# blimpy.net
KiCad netlist of a schematic drawn in EAGLE
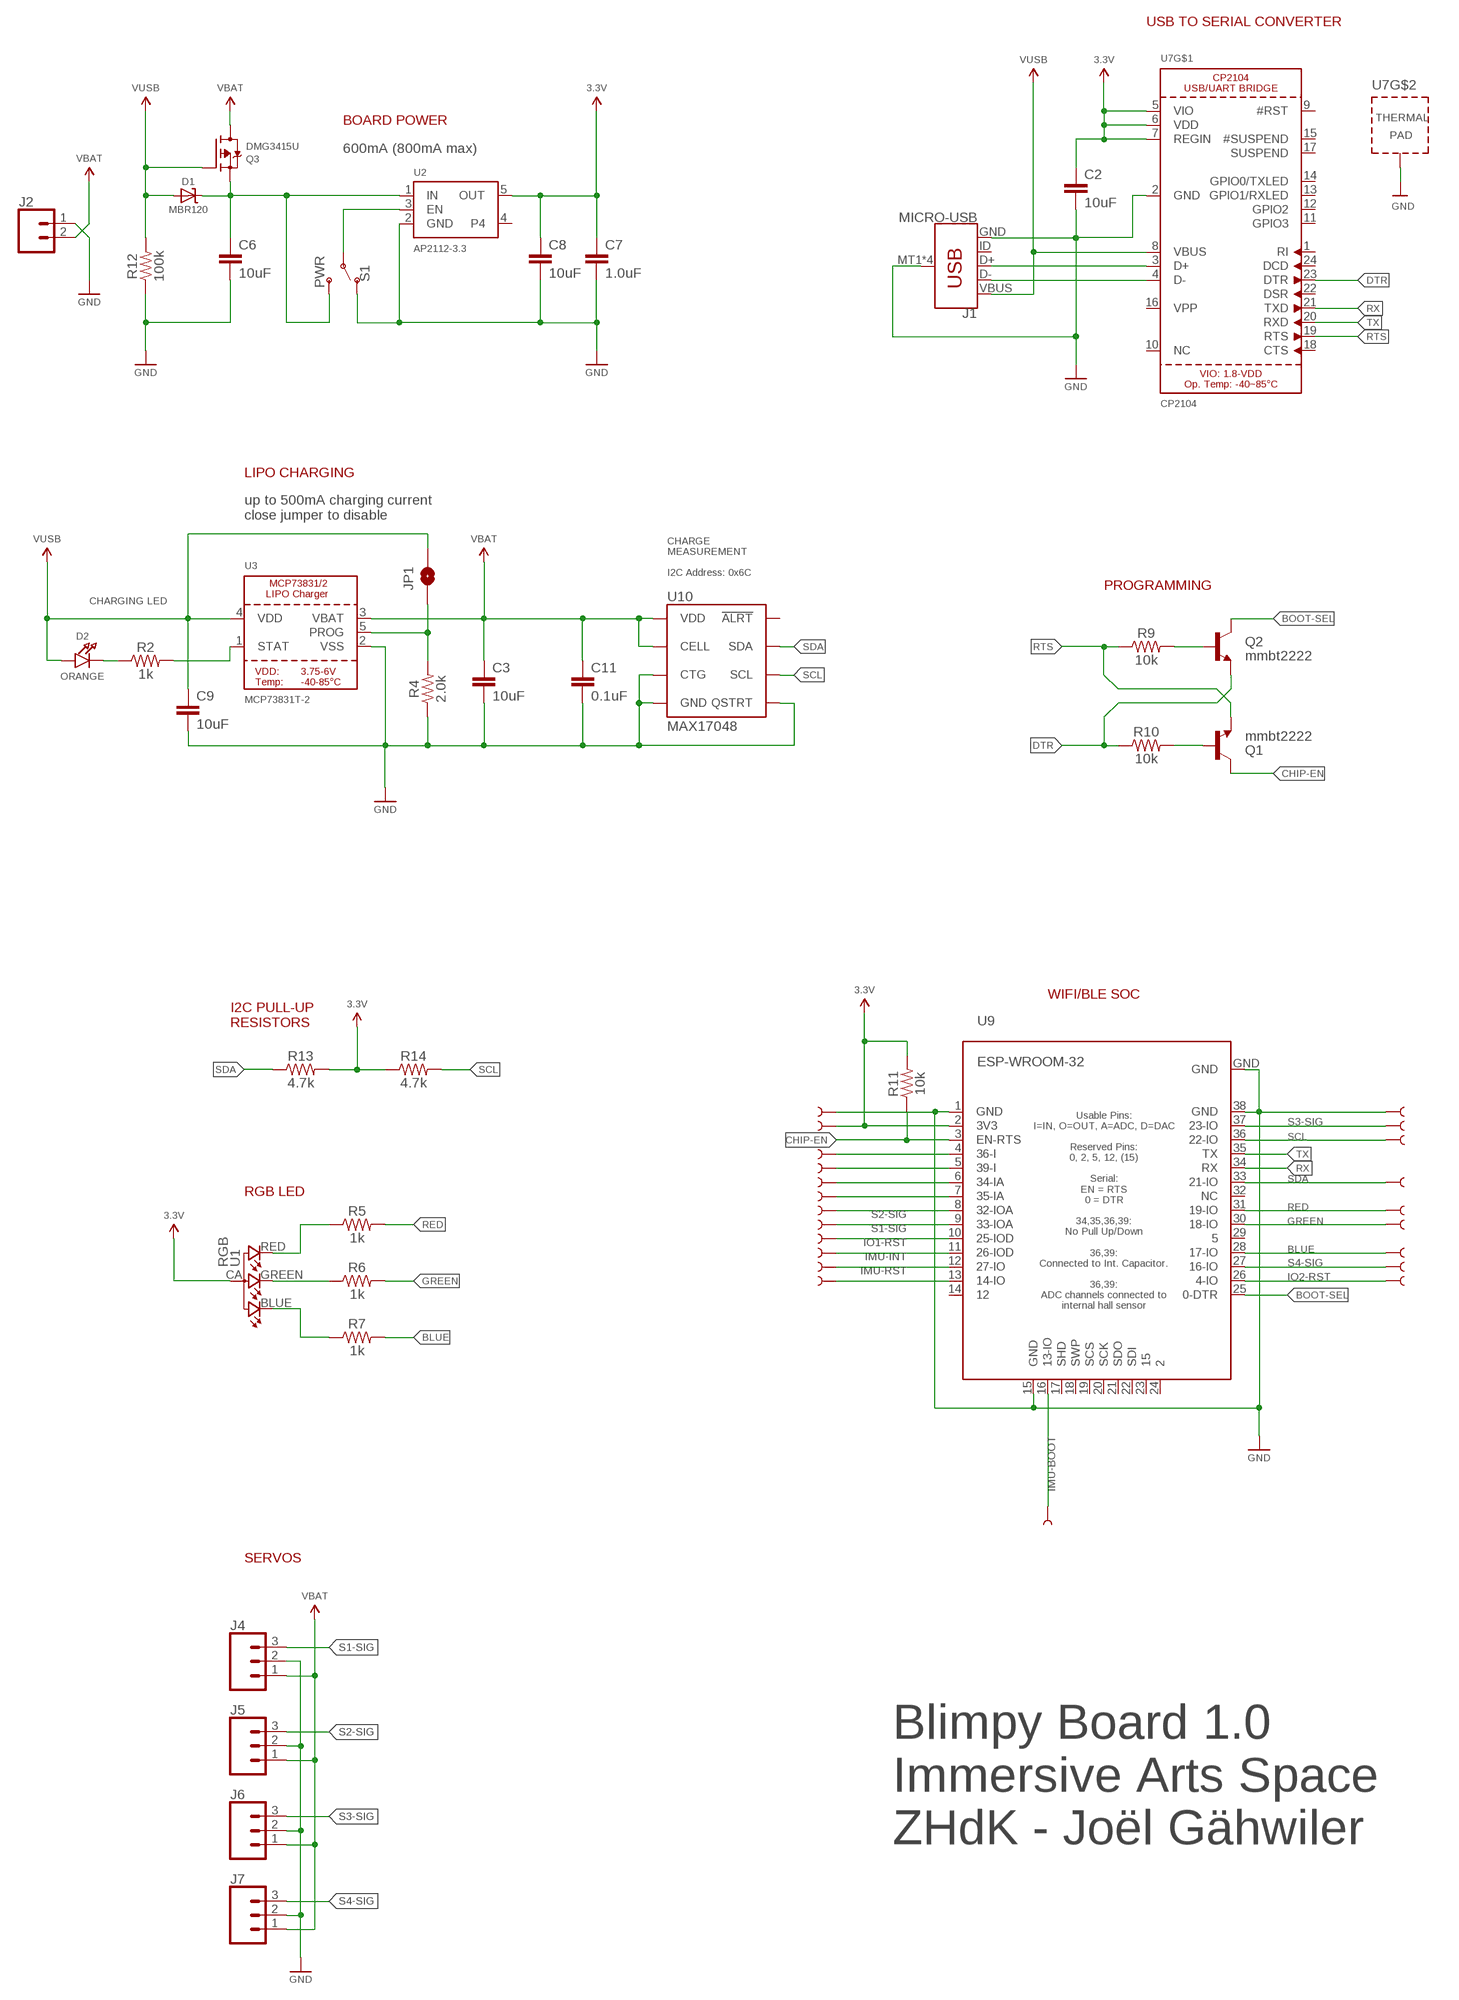
[diagram p0: schematic, sheet 1, part 1 of 2]
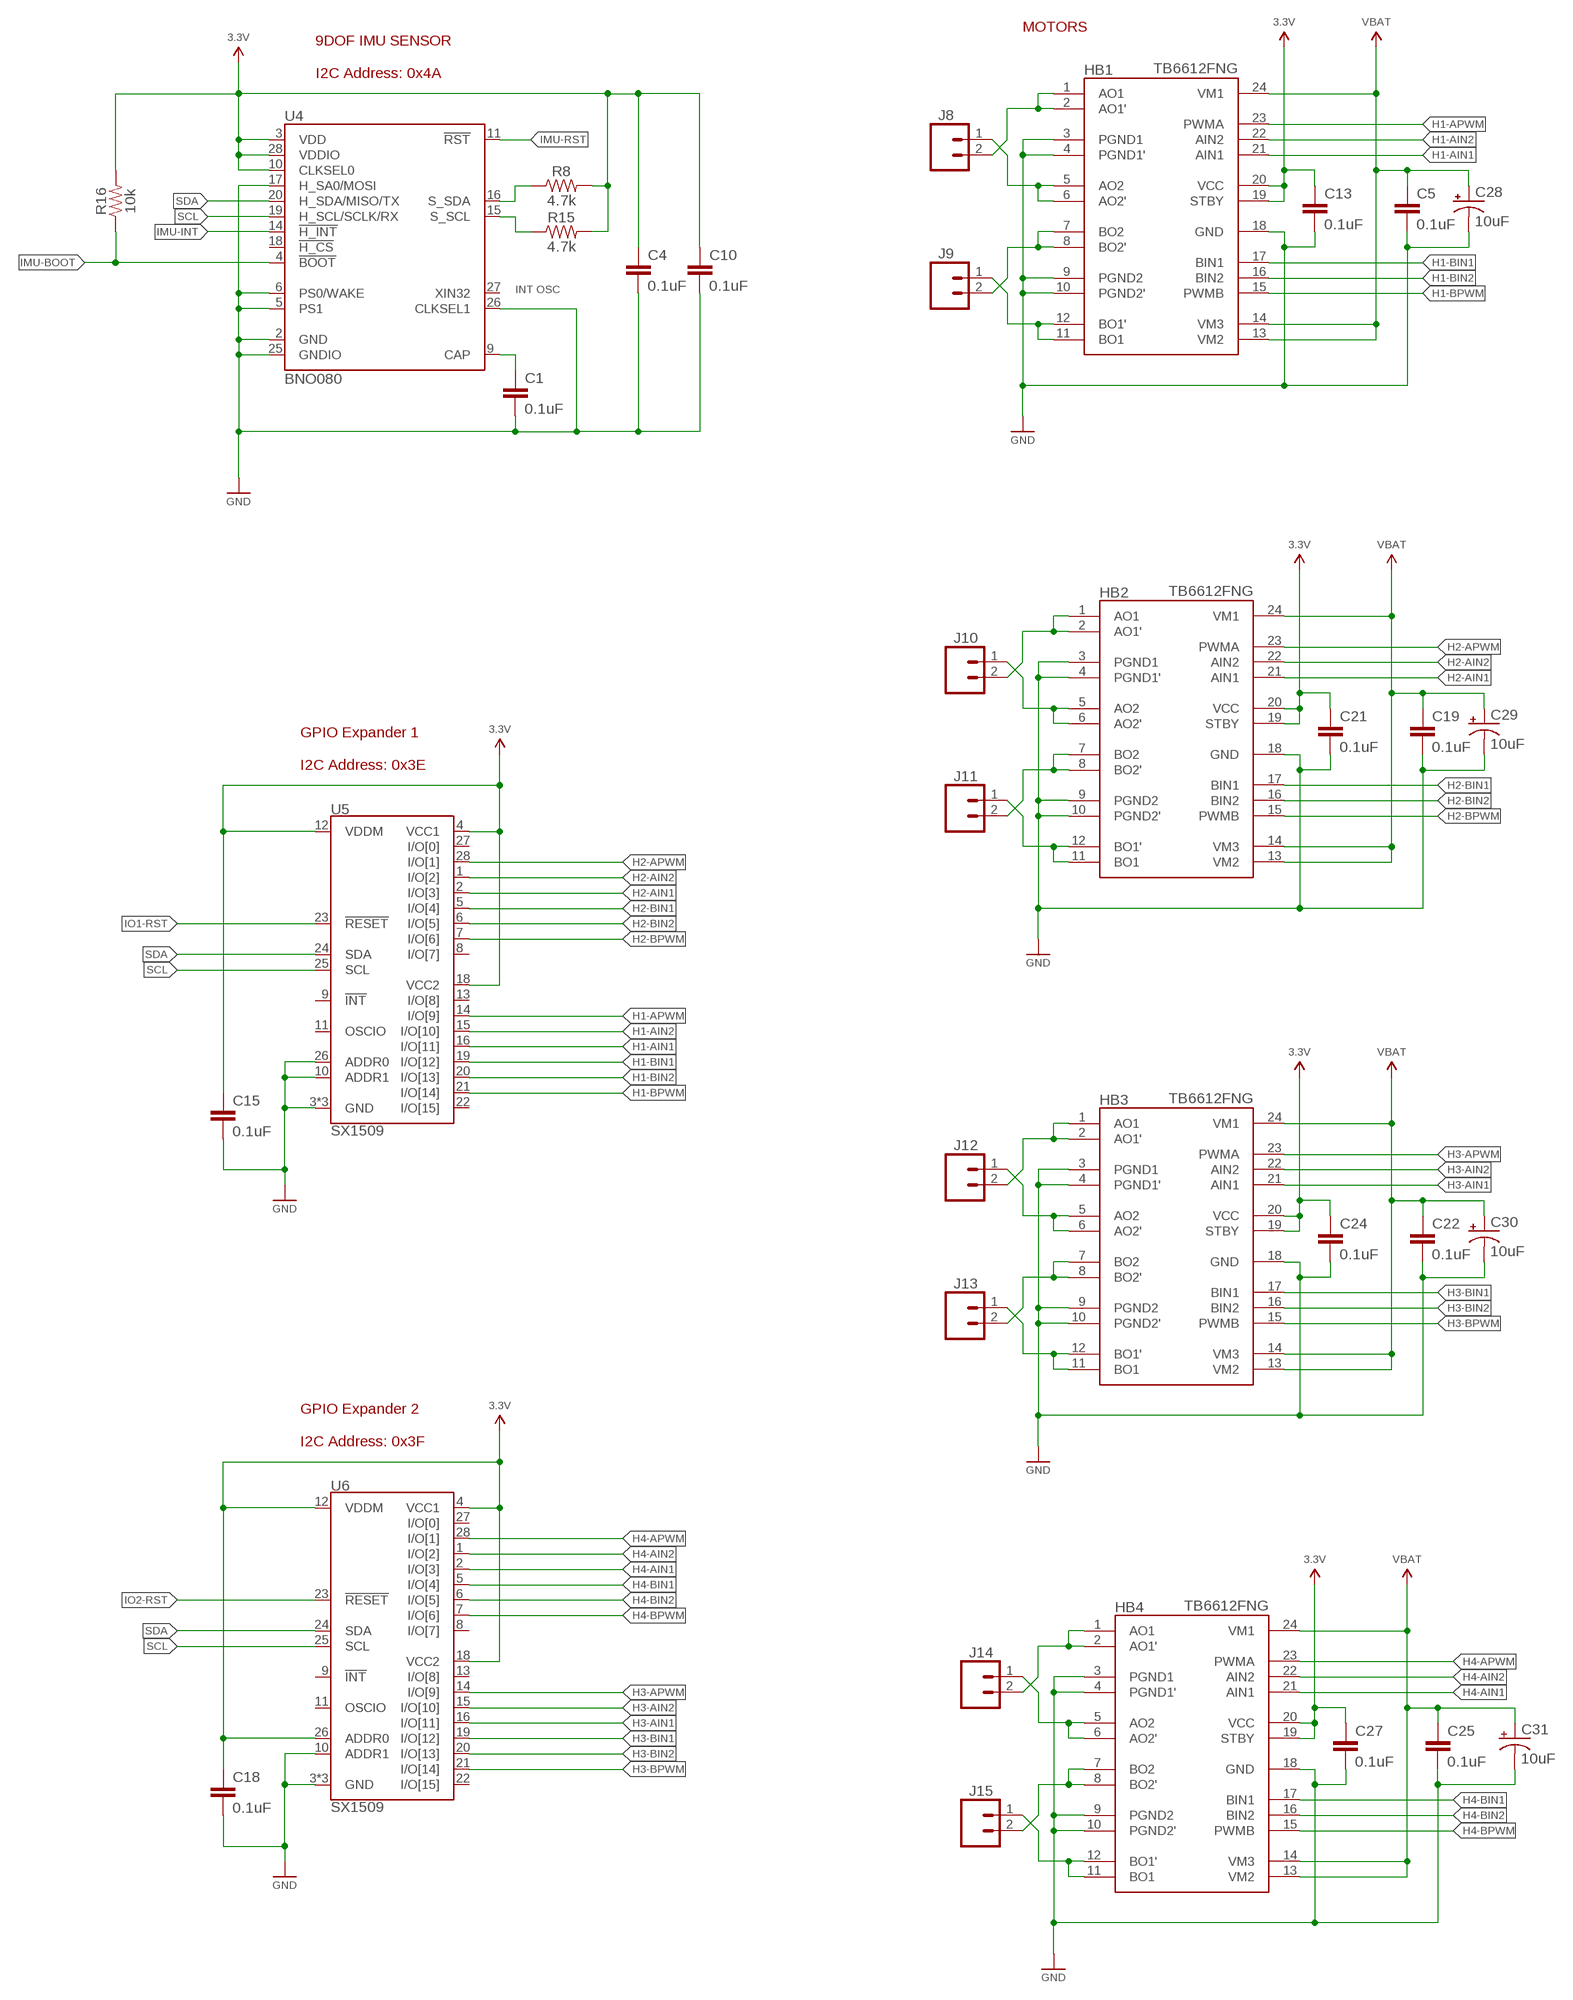
[diagram p1: schematic, sheet 1, part 2 of 2]

(export (version "E")
  (design (tool "Eeschema 10.0.6"))
  (components
    (comp (ref "C1")
      (value "0.1uF")
      (footprint "eagle-import:0603")
      (libsource (lib "eagle-import") (part "0.1UF-0603-25V-5%"))
    )
    (comp (ref "C2")
      (value "10uF")
      (footprint "eagle-import:0603")
      (libsource (lib "eagle-import") (part "10UF-0603-6.3V-20%"))
    )
    (comp (ref "C3")
      (value "10uF")
      (footprint "eagle-import:0603")
      (libsource (lib "eagle-import") (part "10UF-0603-6.3V-20%"))
    )
    (comp (ref "C4")
      (value "0.1uF")
      (footprint "eagle-import:0603")
      (libsource (lib "eagle-import") (part "0.1UF-0603-25V-5%"))
    )
    (comp (ref "C5")
      (value "0.1uF")
      (footprint "eagle-import:0603")
      (libsource (lib "eagle-import") (part "0.1UF-0603-25V-5%"))
    )
    (comp (ref "C6")
      (value "10uF")
      (footprint "eagle-import:0603")
      (libsource (lib "eagle-import") (part "10UF-0603-6.3V-20%"))
    )
    (comp (ref "C7")
      (value "1.0uF")
      (footprint "eagle-import:0603")
      (libsource (lib "eagle-import") (part "1.0UF-0603-16V-10%"))
    )
    (comp (ref "C8")
      (value "10uF")
      (footprint "eagle-import:0603")
      (libsource (lib "eagle-import") (part "10UF-0603-6.3V-20%"))
    )
    (comp (ref "C9")
      (value "10uF")
      (footprint "eagle-import:0603")
      (libsource (lib "eagle-import") (part "10UF-0603-6.3V-20%"))
    )
    (comp (ref "C10")
      (value "0.1uF")
      (footprint "eagle-import:0603")
      (libsource (lib "eagle-import") (part "0.1UF-0603-25V-5%"))
    )
    (comp (ref "C11")
      (value "0.1uF")
      (footprint "eagle-import:0603")
      (libsource (lib "eagle-import") (part "SparkFun-Capacitors_510_0.1UF-0603-25V-5%"))
    )
    (comp (ref "C13")
      (value "0.1uF")
      (footprint "eagle-import:0603")
      (libsource (lib "eagle-import") (part "0.1UF-0603-25V-5%"))
    )
    (comp (ref "C15")
      (value "0.1uF")
      (footprint "eagle-import:0603")
      (libsource (lib "eagle-import") (part "SparkFun-Capacitors_510_0.1UF-0603-25V-5%"))
    )
    (comp (ref "C18")
      (value "0.1uF")
      (footprint "eagle-import:0603")
      (libsource (lib "eagle-import") (part "SparkFun-Capacitors_510_0.1UF-0603-25V-5%"))
    )
    (comp (ref "C19")
      (value "0.1uF")
      (footprint "eagle-import:0603")
      (libsource (lib "eagle-import") (part "0.1UF-0603-25V-5%"))
    )
    (comp (ref "C21")
      (value "0.1uF")
      (footprint "eagle-import:0603")
      (libsource (lib "eagle-import") (part "0.1UF-0603-25V-5%"))
    )
    (comp (ref "C22")
      (value "0.1uF")
      (footprint "eagle-import:0603")
      (libsource (lib "eagle-import") (part "0.1UF-0603-25V-5%"))
    )
    (comp (ref "C24")
      (value "0.1uF")
      (footprint "eagle-import:0603")
      (libsource (lib "eagle-import") (part "0.1UF-0603-25V-5%"))
    )
    (comp (ref "C25")
      (value "0.1uF")
      (footprint "eagle-import:0603")
      (libsource (lib "eagle-import") (part "0.1UF-0603-25V-5%"))
    )
    (comp (ref "C27")
      (value "0.1uF")
      (footprint "eagle-import:0603")
      (libsource (lib "eagle-import") (part "0.1UF-0603-25V-5%"))
    )
    (comp (ref "C28")
      (value "10uF")
      (footprint "eagle-import:EIA3216")
      (libsource (lib "eagle-import") (part "10UF-POLAR-EIA3216-16V-10%(TANT)"))
    )
    (comp (ref "C29")
      (value "10uF")
      (footprint "eagle-import:EIA3216")
      (libsource (lib "eagle-import") (part "10UF-POLAR-EIA3216-16V-10%(TANT)"))
    )
    (comp (ref "C30")
      (value "10uF")
      (footprint "eagle-import:EIA3216")
      (libsource (lib "eagle-import") (part "10UF-POLAR-EIA3216-16V-10%(TANT)"))
    )
    (comp (ref "C31")
      (value "10uF")
      (footprint "eagle-import:EIA3216")
      (libsource (lib "eagle-import") (part "10UF-POLAR-EIA3216-16V-10%(TANT)"))
    )
    (comp (ref "D1")
      (value "MBR120")
      (footprint "eagle-import:SOD-123")
      (libsource (lib "eagle-import") (part "DIODE-SCHOTTKYSOD-123"))
    )
    (comp (ref "D2")
      (value "ORANGE")
      (footprint "eagle-import:CHIPLED_0805_NOOUTLINE")
      (libsource (lib "eagle-import") (part "LED0805_NOOUTLINE"))
    )
    (comp (ref "HB1")
      (value "TB6612FNG")
      (footprint "eagle-import:SSOP24")
      (libsource (lib "eagle-import") (part "TB6612FNG"))
    )
    (comp (ref "HB2")
      (value "TB6612FNG")
      (footprint "eagle-import:SSOP24")
      (libsource (lib "eagle-import") (part "TB6612FNG"))
    )
    (comp (ref "HB3")
      (value "TB6612FNG")
      (footprint "eagle-import:SSOP24")
      (libsource (lib "eagle-import") (part "TB6612FNG"))
    )
    (comp (ref "HB4")
      (value "TB6612FNG")
      (footprint "eagle-import:SSOP24")
      (libsource (lib "eagle-import") (part "TB6612FNG"))
    )
    (comp (ref "J1")
      (value "MICRO-USB")
      (footprint "eagle-import:USB-MICROB")
      (libsource (lib "eagle-import") (part "USB_MICRO-B_SMT"))
    )
    (comp (ref "J2")
      (value "CONN_02-JST-2MM-SMT")
      (footprint "eagle-import:JST-2-SMD")
      (libsource (lib "eagle-import") (part "CONN_02-JST-2MM-SMT"))
    )
    (comp (ref "J4")
      (value "3-PIN SMD")
      (footprint "eagle-import:JST-3-SMD")
      (libsource (lib "eagle-import") (part "CONN_03JST-SMD"))
    )
    (comp (ref "J5")
      (value "3-PIN SMD")
      (footprint "eagle-import:JST-3-SMD")
      (libsource (lib "eagle-import") (part "CONN_03JST-SMD"))
    )
    (comp (ref "J6")
      (value "3-PIN SMD")
      (footprint "eagle-import:JST-3-SMD")
      (libsource (lib "eagle-import") (part "CONN_03JST-SMD"))
    )
    (comp (ref "J7")
      (value "3-PIN SMD")
      (footprint "eagle-import:JST-3-SMD")
      (libsource (lib "eagle-import") (part "CONN_03JST-SMD"))
    )
    (comp (ref "J8")
      (value "CONN_02-JST-2MM-SMT")
      (footprint "eagle-import:JST-2-SMD")
      (libsource (lib "eagle-import") (part "CONN_02-JST-2MM-SMT"))
    )
    (comp (ref "J9")
      (value "CONN_02-JST-2MM-SMT")
      (footprint "eagle-import:JST-2-SMD")
      (libsource (lib "eagle-import") (part "CONN_02-JST-2MM-SMT"))
    )
    (comp (ref "J10")
      (value "CONN_02-JST-2MM-SMT")
      (footprint "eagle-import:JST-2-SMD")
      (libsource (lib "eagle-import") (part "CONN_02-JST-2MM-SMT"))
    )
    (comp (ref "J11")
      (value "CONN_02-JST-2MM-SMT")
      (footprint "eagle-import:JST-2-SMD")
      (libsource (lib "eagle-import") (part "CONN_02-JST-2MM-SMT"))
    )
    (comp (ref "J12")
      (value "CONN_02-JST-2MM-SMT")
      (footprint "eagle-import:JST-2-SMD")
      (libsource (lib "eagle-import") (part "CONN_02-JST-2MM-SMT"))
    )
    (comp (ref "J13")
      (value "CONN_02-JST-2MM-SMT")
      (footprint "eagle-import:JST-2-SMD")
      (libsource (lib "eagle-import") (part "CONN_02-JST-2MM-SMT"))
    )
    (comp (ref "J14")
      (value "CONN_02-JST-2MM-SMT")
      (footprint "eagle-import:JST-2-SMD")
      (libsource (lib "eagle-import") (part "CONN_02-JST-2MM-SMT"))
    )
    (comp (ref "J15")
      (value "CONN_02-JST-2MM-SMT")
      (footprint "eagle-import:JST-2-SMD")
      (libsource (lib "eagle-import") (part "CONN_02-JST-2MM-SMT"))
    )
    (comp (ref "JP1")
      (value "JUMPER-SMT_2_NO_SILK")
      (footprint "eagle-import:SMT-JUMPER_2_NO_SILK")
      (libsource (lib "eagle-import") (part "JUMPER-SMT_2_NO_SILK"))
    )
    (comp (ref "Q1")
      (value "mmbt2222")
      (footprint "eagle-import:SOT23-3")
      (libsource (lib "eagle-import") (part "TRANSISTOR_NPNSOT23-3"))
    )
    (comp (ref "Q2")
      (value "mmbt2222")
      (footprint "eagle-import:SOT23-3")
      (libsource (lib "eagle-import") (part "TRANSISTOR_NPNSOT23-3"))
    )
    (comp (ref "Q3")
      (value "DMG3415U")
      (footprint "eagle-import:SOT23-R")
      (libsource (lib "eagle-import") (part "MOSFET-P"))
    )
    (comp (ref "R2")
      (value "1k")
      (footprint "eagle-import:0603")
      (libsource (lib "eagle-import") (part "1KOHM-0603-1/10W-1%"))
    )
    (comp (ref "R4")
      (value "2.0k")
      (footprint "eagle-import:0603")
      (libsource (lib "eagle-import") (part "2.0KOHM-0603-1/10W-5%"))
    )
    (comp (ref "R5")
      (value "1k")
      (footprint "eagle-import:0603")
      (libsource (lib "eagle-import") (part "1KOHM-0603-1/10W-1%"))
    )
    (comp (ref "R6")
      (value "1k")
      (footprint "eagle-import:0603")
      (libsource (lib "eagle-import") (part "1KOHM-0603-1/10W-1%"))
    )
    (comp (ref "R7")
      (value "1k")
      (footprint "eagle-import:0603")
      (libsource (lib "eagle-import") (part "1KOHM-0603-1/10W-1%"))
    )
    (comp (ref "R8")
      (value "4.7k")
      (footprint "eagle-import:0603")
      (libsource (lib "eagle-import") (part "4.7KOHM-0603-1/10W-1%"))
    )
    (comp (ref "R9")
      (value "10k")
      (footprint "eagle-import:0603")
      (libsource (lib "eagle-import") (part "10KOHM-0603-1/10W-1%"))
    )
    (comp (ref "R10")
      (value "10k")
      (footprint "eagle-import:0603")
      (libsource (lib "eagle-import") (part "10KOHM-0603-1/10W-1%"))
    )
    (comp (ref "R11")
      (value "10k")
      (footprint "eagle-import:0603")
      (libsource (lib "eagle-import") (part "10KOHM-0603-1/10W-1%"))
    )
    (comp (ref "R12")
      (value "100k")
      (footprint "eagle-import:0603")
      (libsource (lib "eagle-import") (part "100KOHM-0603-1/10W-1%"))
    )
    (comp (ref "R13")
      (value "4.7k")
      (footprint "eagle-import:0603")
      (libsource (lib "eagle-import") (part "4.7KOHM-0603-1/10W-1%"))
    )
    (comp (ref "R14")
      (value "4.7k")
      (footprint "eagle-import:0603")
      (libsource (lib "eagle-import") (part "4.7KOHM-0603-1/10W-1%"))
    )
    (comp (ref "R15")
      (value "4.7k")
      (footprint "eagle-import:0603")
      (libsource (lib "eagle-import") (part "4.7KOHM-0603-1/10W-1%"))
    )
    (comp (ref "R16")
      (value "10k")
      (footprint "eagle-import:0603")
      (libsource (lib "eagle-import") (part "10KOHM-0603-1/10W-1%"))
    )
    (comp (ref "S1")
      (value "PWR")
      (footprint "eagle-import:SWITCH_SPST_SMD_A")
      (libsource (lib "eagle-import") (part "SWITCH-SPDT-SMD-RIGHT-ANGLE"))
    )
    (comp (ref "TP1")
      (value "TEST-POINT3")
      (footprint "eagle-import:PAD.03X.03")
      (libsource (lib "eagle-import") (part "TEST-POINT3"))
    )
    (comp (ref "TP2")
      (value "TEST-POINT3")
      (footprint "eagle-import:PAD.03X.03")
      (libsource (lib "eagle-import") (part "TEST-POINT3"))
    )
    (comp (ref "TP3")
      (value "TEST-POINT3")
      (footprint "eagle-import:PAD.03X.03")
      (libsource (lib "eagle-import") (part "TEST-POINT3"))
    )
    (comp (ref "TP4")
      (value "TEST-POINT3")
      (footprint "eagle-import:PAD.03X.03")
      (libsource (lib "eagle-import") (part "TEST-POINT3"))
    )
    (comp (ref "TP5")
      (value "TEST-POINT3")
      (footprint "eagle-import:PAD.03X.03")
      (libsource (lib "eagle-import") (part "TEST-POINT3"))
    )
    (comp (ref "TP6")
      (value "TEST-POINT3")
      (footprint "eagle-import:PAD.03X.03")
      (libsource (lib "eagle-import") (part "TEST-POINT3"))
    )
    (comp (ref "TP7")
      (value "TEST-POINT3")
      (footprint "eagle-import:PAD.03X.03")
      (libsource (lib "eagle-import") (part "TEST-POINT3"))
    )
    (comp (ref "TP8")
      (value "TEST-POINT3")
      (footprint "eagle-import:PAD.03X.03")
      (libsource (lib "eagle-import") (part "TEST-POINT3"))
    )
    (comp (ref "TP9")
      (value "TEST-POINT3")
      (footprint "eagle-import:PAD.03X.03")
      (libsource (lib "eagle-import") (part "TEST-POINT3"))
    )
    (comp (ref "TP10")
      (value "TEST-POINT3")
      (footprint "eagle-import:PAD.03X.03")
      (libsource (lib "eagle-import") (part "TEST-POINT3"))
    )
    (comp (ref "TP11")
      (value "TEST-POINT3")
      (footprint "eagle-import:PAD.03X.03")
      (libsource (lib "eagle-import") (part "TEST-POINT3"))
    )
    (comp (ref "TP12")
      (value "TEST-POINT3")
      (footprint "eagle-import:PAD.03X.03")
      (libsource (lib "eagle-import") (part "TEST-POINT3"))
    )
    (comp (ref "TP13")
      (value "TEST-POINT3")
      (footprint "eagle-import:PAD.03X.03")
      (libsource (lib "eagle-import") (part "TEST-POINT3"))
    )
    (comp (ref "TP14")
      (value "TEST-POINT3")
      (footprint "eagle-import:PAD.03X.03")
      (libsource (lib "eagle-import") (part "TEST-POINT3"))
    )
    (comp (ref "TP15")
      (value "TEST-POINT3")
      (footprint "eagle-import:PAD.03X.03")
      (libsource (lib "eagle-import") (part "TEST-POINT3"))
    )
    (comp (ref "TP16")
      (value "TEST-POINT3")
      (footprint "eagle-import:PAD.03X.03")
      (libsource (lib "eagle-import") (part "TEST-POINT3"))
    )
    (comp (ref "TP17")
      (value "TEST-POINT3")
      (footprint "eagle-import:PAD.03X.03")
      (libsource (lib "eagle-import") (part "TEST-POINT3"))
    )
    (comp (ref "TP18")
      (value "TEST-POINT3")
      (footprint "eagle-import:PAD.03X.03")
      (libsource (lib "eagle-import") (part "TEST-POINT3"))
    )
    (comp (ref "TP19")
      (value "TEST-POINT3")
      (footprint "eagle-import:PAD.03X.03")
      (libsource (lib "eagle-import") (part "TEST-POINT3"))
    )
    (comp (ref "TP20")
      (value "TEST-POINT3")
      (footprint "eagle-import:PAD.03X.03")
      (libsource (lib "eagle-import") (part "TEST-POINT3"))
    )
    (comp (ref "TP21")
      (value "TEST-POINT3")
      (footprint "eagle-import:PAD.03X.03")
      (libsource (lib "eagle-import") (part "TEST-POINT3"))
    )
    (comp (ref "TP22")
      (value "TEST-POINT3")
      (footprint "eagle-import:PAD.03X.03")
      (libsource (lib "eagle-import") (part "TEST-POINT3"))
    )
    (comp (ref "U1")
      (value "RGB")
      (footprint "eagle-import:PLCC4-2MM-RGB")
      (libsource (lib "eagle-import") (part "RGB-LED-CLMVB-FKARGB"))
    )
    (comp (ref "U2")
      (value "AP2112-3.3")
      (footprint "eagle-import:SOT23-5")
      (libsource (lib "eagle-import") (part "VREG_SOT23-5"))
    )
    (comp (ref "U3")
      (value "MCP73831T-2")
      (footprint "eagle-import:SOT23-5")
      (libsource (lib "eagle-import") (part "MCP73831/2"))
    )
    (comp (ref "U4")
      (value "BNO080")
      (footprint "eagle-import:LGA-28")
      (libsource (lib "eagle-import") (part "BNO080"))
    )
    (comp (ref "U5")
      (value "SX1509")
      (footprint "eagle-import:QFN-28")
      (libsource (lib "eagle-import") (part "SX1509"))
    )
    (comp (ref "U6")
      (value "SX1509")
      (footprint "eagle-import:QFN-28")
      (libsource (lib "eagle-import") (part "SX1509"))
    )
    (comp (ref "U7")
      (value "CP2104")
      (footprint "eagle-import:QFN24_4MM_SMSC")
      (libsource (lib "eagle-import") (part "CP2104"))
    )
    (comp (ref "U9")
      (value "ESP-WROOM-32")
      (footprint "eagle-import:ESP-WROOM-32")
      (libsource (lib "eagle-import") (part "ESP-WROOM-32"))
    )
    (comp (ref "U10")
      (value "MAX17048")
      (footprint "eagle-import:DFN-8")
      (libsource (lib "eagle-import") (part "MAX17048DFN8"))
    )
  )
  (nets
    (net (code "1") (name "3.3V") (class "Default")
      (node (ref "C10") (pin "1") (pinfunction "1_1") (pintype "passive"))
      (node (ref "C13") (pin "1") (pinfunction "1_1") (pintype "passive"))
      (node (ref "C15") (pin "1") (pinfunction "1_1") (pintype "passive"))
      (node (ref "C18") (pin "1") (pinfunction "1_1") (pintype "passive"))
      (node (ref "C2") (pin "1") (pinfunction "1_1") (pintype "passive"))
      (node (ref "C21") (pin "1") (pinfunction "1_1") (pintype "passive"))
      (node (ref "C24") (pin "1") (pinfunction "1_1") (pintype "passive"))
      (node (ref "C27") (pin "1") (pinfunction "1_1") (pintype "passive"))
      (node (ref "C4") (pin "1") (pinfunction "1_1") (pintype "passive"))
      (node (ref "C7") (pin "1") (pinfunction "1_1") (pintype "passive"))
      (node (ref "C8") (pin "1") (pinfunction "1_1") (pintype "passive"))
      (node (ref "HB1") (pin "19") (pinfunction "STBY_19") (pintype "input"))
      (node (ref "HB1") (pin "20") (pinfunction "VCC_20") (pintype "power_in"))
      (node (ref "HB2") (pin "19") (pinfunction "STBY_19") (pintype "input"))
      (node (ref "HB2") (pin "20") (pinfunction "VCC_20") (pintype "power_in"))
      (node (ref "HB3") (pin "19") (pinfunction "STBY_19") (pintype "input"))
      (node (ref "HB3") (pin "20") (pinfunction "VCC_20") (pintype "power_in"))
      (node (ref "HB4") (pin "19") (pinfunction "STBY_19") (pintype "input"))
      (node (ref "HB4") (pin "20") (pinfunction "VCC_20") (pintype "power_in"))
      (node (ref "R11") (pin "2") (pinfunction "2_2") (pintype "passive"))
      (node (ref "R13") (pin "2") (pinfunction "2_2") (pintype "passive"))
      (node (ref "R14") (pin "1") (pinfunction "1_1") (pintype "passive"))
      (node (ref "R15") (pin "2") (pinfunction "2_2") (pintype "passive"))
      (node (ref "R16") (pin "2") (pinfunction "2_2") (pintype "passive"))
      (node (ref "R8") (pin "2") (pinfunction "2_2") (pintype "passive"))
      (node (ref "TP11") (pin "P$1") (pinfunction "1_P$1") (pintype "bidirectional"))
      (node (ref "U1") (pin "CA") (pinfunction "1_CA") (pintype "passive"))
      (node (ref "U2") (pin "5") (pinfunction "OUT_5") (pintype "power_in"))
      (node (ref "U4") (pin "10") (pinfunction "CLKSEL0_10") (pintype "bidirectional"))
      (node (ref "U4") (pin "28") (pinfunction "VDDIO_28") (pintype "bidirectional"))
      (node (ref "U4") (pin "3") (pinfunction "VDD_3") (pintype "bidirectional"))
      (node (ref "U5") (pin "12") (pinfunction "VDDM_12") (pintype "bidirectional"))
      (node (ref "U5") (pin "18") (pinfunction "VCC2_18") (pintype "bidirectional"))
      (node (ref "U5") (pin "4") (pinfunction "VCC1_4") (pintype "bidirectional"))
      (node (ref "U6") (pin "12") (pinfunction "VDDM_12") (pintype "bidirectional"))
      (node (ref "U6") (pin "18") (pinfunction "VCC2_18") (pintype "bidirectional"))
      (node (ref "U6") (pin "26") (pinfunction "ADDR0_26") (pintype "bidirectional"))
      (node (ref "U6") (pin "4") (pinfunction "VCC1_4") (pintype "bidirectional"))
      (node (ref "U7") (pin "5") (pinfunction "VIO_5") (pintype "power_in"))
      (node (ref "U7") (pin "6") (pinfunction "VDD_6") (pintype "power_in"))
      (node (ref "U7") (pin "7") (pinfunction "REGIN_7") (pintype "power_in"))
      (node (ref "U9") (pin "2") (pinfunction "3V3_2") (pintype "bidirectional"))
    )
    (net (code "2") (name "BLUE") (class "Default")
      (node (ref "R7") (pin "2") (pinfunction "2_2") (pintype "passive"))
      (node (ref "TP22") (pin "P$1") (pinfunction "1_P$1") (pintype "bidirectional"))
      (node (ref "U9") (pin "28") (pinfunction "17-IO_28") (pintype "bidirectional"))
    )
    (net (code "3") (name "BOOT-SEL") (class "Default")
      (node (ref "Q2") (pin "3") (pinfunction "C_3") (pintype "passive"))
      (node (ref "U9") (pin "25") (pinfunction "0-DTR_25") (pintype "bidirectional"))
    )
    (net (code "4") (name "CHIP-EN") (class "Default")
      (node (ref "Q1") (pin "3") (pinfunction "C_3") (pintype "passive"))
      (node (ref "R11") (pin "1") (pinfunction "1_1") (pintype "passive"))
      (node (ref "U9") (pin "3") (pinfunction "EN-RTS_3") (pintype "bidirectional"))
    )
    (net (code "5") (name "DTR") (class "Default")
      (node (ref "Q2") (pin "2") (pinfunction "E_2") (pintype "passive"))
      (node (ref "R10") (pin "1") (pinfunction "1_1") (pintype "passive"))
      (node (ref "U7") (pin "23") (pinfunction "DTR_23") (pintype "output"))
    )
    (net (code "6") (name "GND") (class "Default")
      (node (ref "C1") (pin "2") (pinfunction "2_2") (pintype "passive"))
      (node (ref "C10") (pin "2") (pinfunction "2_2") (pintype "passive"))
      (node (ref "C11") (pin "2") (pinfunction "2_2") (pintype "passive"))
      (node (ref "C13") (pin "2") (pinfunction "2_2") (pintype "passive"))
      (node (ref "C15") (pin "2") (pinfunction "2_2") (pintype "passive"))
      (node (ref "C18") (pin "2") (pinfunction "2_2") (pintype "passive"))
      (node (ref "C19") (pin "2") (pinfunction "2_2") (pintype "passive"))
      (node (ref "C2") (pin "2") (pinfunction "2_2") (pintype "passive"))
      (node (ref "C21") (pin "2") (pinfunction "2_2") (pintype "passive"))
      (node (ref "C22") (pin "2") (pinfunction "2_2") (pintype "passive"))
      (node (ref "C24") (pin "2") (pinfunction "2_2") (pintype "passive"))
      (node (ref "C25") (pin "2") (pinfunction "2_2") (pintype "passive"))
      (node (ref "C27") (pin "2") (pinfunction "2_2") (pintype "passive"))
      (node (ref "C28") (pin "-") (pinfunction "-_-") (pintype "passive"))
      (node (ref "C29") (pin "-") (pinfunction "-_-") (pintype "passive"))
      (node (ref "C3") (pin "2") (pinfunction "2_2") (pintype "passive"))
      (node (ref "C30") (pin "-") (pinfunction "-_-") (pintype "passive"))
      (node (ref "C31") (pin "-") (pinfunction "-_-") (pintype "passive"))
      (node (ref "C4") (pin "2") (pinfunction "2_2") (pintype "passive"))
      (node (ref "C5") (pin "2") (pinfunction "2_2") (pintype "passive"))
      (node (ref "C6") (pin "2") (pinfunction "2_2") (pintype "passive"))
      (node (ref "C7") (pin "2") (pinfunction "2_2") (pintype "passive"))
      (node (ref "C8") (pin "2") (pinfunction "2_2") (pintype "passive"))
      (node (ref "C9") (pin "2") (pinfunction "2_2") (pintype "passive"))
      (node (ref "HB1") (pin "10") (pinfunction "PGND2'_10") (pintype "power_in"))
      (node (ref "HB1") (pin "18") (pinfunction "GND_18") (pintype "power_in"))
      (node (ref "HB1") (pin "3") (pinfunction "PGND1_3") (pintype "power_in"))
      (node (ref "HB1") (pin "4") (pinfunction "PGND1'_4") (pintype "power_in"))
      (node (ref "HB1") (pin "9") (pinfunction "PGND2_9") (pintype "power_in"))
      (node (ref "HB2") (pin "10") (pinfunction "PGND2'_10") (pintype "power_in"))
      (node (ref "HB2") (pin "18") (pinfunction "GND_18") (pintype "power_in"))
      (node (ref "HB2") (pin "3") (pinfunction "PGND1_3") (pintype "power_in"))
      (node (ref "HB2") (pin "4") (pinfunction "PGND1'_4") (pintype "power_in"))
      (node (ref "HB2") (pin "9") (pinfunction "PGND2_9") (pintype "power_in"))
      (node (ref "HB3") (pin "10") (pinfunction "PGND2'_10") (pintype "power_in"))
      (node (ref "HB3") (pin "18") (pinfunction "GND_18") (pintype "power_in"))
      (node (ref "HB3") (pin "3") (pinfunction "PGND1_3") (pintype "power_in"))
      (node (ref "HB3") (pin "4") (pinfunction "PGND1'_4") (pintype "power_in"))
      (node (ref "HB3") (pin "9") (pinfunction "PGND2_9") (pintype "power_in"))
      (node (ref "HB4") (pin "10") (pinfunction "PGND2'_10") (pintype "power_in"))
      (node (ref "HB4") (pin "18") (pinfunction "GND_18") (pintype "power_in"))
      (node (ref "HB4") (pin "3") (pinfunction "PGND1_3") (pintype "power_in"))
      (node (ref "HB4") (pin "4") (pinfunction "PGND1'_4") (pintype "power_in"))
      (node (ref "HB4") (pin "9") (pinfunction "PGND2_9") (pintype "power_in"))
      (node (ref "J1") (pin "GND") (pinfunction "GND_GND") (pintype "power_in"))
      (node (ref "J1") (pin "MT1") (pinfunction "SHIELD_MT1") (pintype "bidirectional"))
      (node (ref "J1") (pin "MT2") (pinfunction "SHIELD_MT2") (pintype "bidirectional"))
      (node (ref "J1") (pin "P$1") (pinfunction "SHIELD_P$1") (pintype "bidirectional"))
      (node (ref "J1") (pin "P$2") (pinfunction "SHIELD_P$2") (pintype "bidirectional"))
      (node (ref "J2") (pin "1") (pinfunction "2_1") (pintype "passive"))
      (node (ref "J4") (pin "2") (pinfunction "2_2") (pintype "passive"))
      (node (ref "J5") (pin "2") (pinfunction "2_2") (pintype "passive"))
      (node (ref "J6") (pin "2") (pinfunction "2_2") (pintype "passive"))
      (node (ref "J7") (pin "2") (pinfunction "2_2") (pintype "passive"))
      (node (ref "R12") (pin "1") (pinfunction "1_1") (pintype "passive"))
      (node (ref "R4") (pin "1") (pinfunction "1_1") (pintype "passive"))
      (node (ref "S1") (pin "1") (pinfunction "O_1") (pintype "passive"))
      (node (ref "TP12") (pin "P$1") (pinfunction "1_P$1") (pintype "bidirectional"))
      (node (ref "TP13") (pin "P$1") (pinfunction "1_P$1") (pintype "bidirectional"))
      (node (ref "U10") (pin "P$1") (pinfunction "CTG_P$1") (pintype "input"))
      (node (ref "U10") (pin "P$4") (pinfunction "GND_P$4") (pintype "bidirectional"))
      (node (ref "U10") (pin "P$6") (pinfunction "QSTRT_P$6") (pintype "bidirectional"))
      (node (ref "U10") (pin "P$9") (pinfunction "GND_P$9") (pintype "bidirectional"))
      (node (ref "U2") (pin "2") (pinfunction "GND_2") (pintype "power_in"))
      (node (ref "U3") (pin "2") (pinfunction "VSS_2") (pintype "power_in"))
      (node (ref "U4") (pin "17") (pinfunction "H_SA0/MOSI_17") (pintype "bidirectional"))
      (node (ref "U4") (pin "2") (pinfunction "GND_2") (pintype "bidirectional"))
      (node (ref "U4") (pin "25") (pinfunction "GNDIO_25") (pintype "bidirectional"))
      (node (ref "U4") (pin "26") (pinfunction "CLKSEL1_26") (pintype "bidirectional"))
      (node (ref "U4") (pin "5") (pinfunction "PS1_5") (pintype "bidirectional"))
      (node (ref "U4") (pin "6") (pinfunction "PS0/WAKE_6") (pintype "bidirectional"))
      (node (ref "U5") (pin "10") (pinfunction "ADDR1_10") (pintype "bidirectional"))
      (node (ref "U5") (pin "17") (pinfunction "GND_17") (pintype "bidirectional"))
      (node (ref "U5") (pin "26") (pinfunction "ADDR0_26") (pintype "bidirectional"))
      (node (ref "U5") (pin "29") (pinfunction "GND_29") (pintype "bidirectional"))
      (node (ref "U5") (pin "3") (pinfunction "GND_3") (pintype "bidirectional"))
      (node (ref "U6") (pin "10") (pinfunction "ADDR1_10") (pintype "bidirectional"))
      (node (ref "U6") (pin "17") (pinfunction "GND_17") (pintype "bidirectional"))
      (node (ref "U6") (pin "29") (pinfunction "GND_29") (pintype "bidirectional"))
      (node (ref "U6") (pin "3") (pinfunction "GND_3") (pintype "bidirectional"))
      (node (ref "U7") (pin "2") (pinfunction "GND_2") (pintype "power_in"))
      (node (ref "U7") (pin "THERM") (pinfunction "TP_THERM") (pintype "power_in"))
      (node (ref "U9") (pin "1") (pinfunction "GND_1") (pintype "bidirectional"))
      (node (ref "U9") (pin "15") (pinfunction "GND_15") (pintype "bidirectional"))
      (node (ref "U9") (pin "38") (pinfunction "GND_38") (pintype "bidirectional"))
      (node (ref "U9") (pin "GND") (pinfunction "GND_GND") (pintype "bidirectional"))
    )
    (net (code "7") (name "GREEN") (class "Default")
      (node (ref "R6") (pin "2") (pinfunction "2_2") (pintype "passive"))
      (node (ref "TP21") (pin "P$1") (pinfunction "1_P$1") (pintype "bidirectional"))
      (node (ref "U9") (pin "30") (pinfunction "18-IO_30") (pintype "bidirectional"))
    )
    (net (code "8") (name "H1-AIN1") (class "Default")
      (node (ref "HB1") (pin "21") (pinfunction "AIN1_21") (pintype "input"))
      (node (ref "U5") (pin "16") (pinfunction "I/O[11]_16") (pintype "bidirectional"))
    )
    (net (code "9") (name "H1-AIN2") (class "Default")
      (node (ref "HB1") (pin "22") (pinfunction "AIN2_22") (pintype "input"))
      (node (ref "U5") (pin "15") (pinfunction "I/O[10]_15") (pintype "bidirectional"))
    )
    (net (code "10") (name "H1-APWM") (class "Default")
      (node (ref "HB1") (pin "23") (pinfunction "PWMA_23") (pintype "input"))
      (node (ref "U5") (pin "14") (pinfunction "I/O[9]_14") (pintype "bidirectional"))
    )
    (net (code "11") (name "H1-BIN1") (class "Default")
      (node (ref "HB1") (pin "17") (pinfunction "BIN1_17") (pintype "input"))
      (node (ref "U5") (pin "19") (pinfunction "I/O[12]_19") (pintype "bidirectional"))
    )
    (net (code "12") (name "H1-BIN2") (class "Default")
      (node (ref "HB1") (pin "16") (pinfunction "BIN2_16") (pintype "input"))
      (node (ref "U5") (pin "20") (pinfunction "I/O[13]_20") (pintype "bidirectional"))
    )
    (net (code "13") (name "H1-BPWM") (class "Default")
      (node (ref "HB1") (pin "15") (pinfunction "PWMB_15") (pintype "input"))
      (node (ref "U5") (pin "21") (pinfunction "I/O[14]_21") (pintype "bidirectional"))
    )
    (net (code "14") (name "H2-AIN1") (class "Default")
      (node (ref "HB2") (pin "21") (pinfunction "AIN1_21") (pintype "input"))
      (node (ref "U5") (pin "2") (pinfunction "I/O[3]_2") (pintype "bidirectional"))
    )
    (net (code "15") (name "H2-AIN2") (class "Default")
      (node (ref "HB2") (pin "22") (pinfunction "AIN2_22") (pintype "input"))
      (node (ref "U5") (pin "1") (pinfunction "I/O[2]_1") (pintype "bidirectional"))
    )
    (net (code "16") (name "H2-APWM") (class "Default")
      (node (ref "HB2") (pin "23") (pinfunction "PWMA_23") (pintype "input"))
      (node (ref "U5") (pin "28") (pinfunction "I/O[1]_28") (pintype "bidirectional"))
    )
    (net (code "17") (name "H2-BIN1") (class "Default")
      (node (ref "HB2") (pin "17") (pinfunction "BIN1_17") (pintype "input"))
      (node (ref "U5") (pin "5") (pinfunction "I/O[4]_5") (pintype "bidirectional"))
    )
    (net (code "18") (name "H2-BIN2") (class "Default")
      (node (ref "HB2") (pin "16") (pinfunction "BIN2_16") (pintype "input"))
      (node (ref "U5") (pin "6") (pinfunction "I/O[5]_6") (pintype "bidirectional"))
    )
    (net (code "19") (name "H2-BPWM") (class "Default")
      (node (ref "HB2") (pin "15") (pinfunction "PWMB_15") (pintype "input"))
      (node (ref "U5") (pin "7") (pinfunction "I/O[6]_7") (pintype "bidirectional"))
    )
    (net (code "20") (name "H3-AIN1") (class "Default")
      (node (ref "HB3") (pin "21") (pinfunction "AIN1_21") (pintype "input"))
      (node (ref "U6") (pin "16") (pinfunction "I/O[11]_16") (pintype "bidirectional"))
    )
    (net (code "21") (name "H3-AIN2") (class "Default")
      (node (ref "HB3") (pin "22") (pinfunction "AIN2_22") (pintype "input"))
      (node (ref "U6") (pin "15") (pinfunction "I/O[10]_15") (pintype "bidirectional"))
    )
    (net (code "22") (name "H3-APWM") (class "Default")
      (node (ref "HB3") (pin "23") (pinfunction "PWMA_23") (pintype "input"))
      (node (ref "U6") (pin "14") (pinfunction "I/O[9]_14") (pintype "bidirectional"))
    )
    (net (code "23") (name "H3-BIN1") (class "Default")
      (node (ref "HB3") (pin "17") (pinfunction "BIN1_17") (pintype "input"))
      (node (ref "U6") (pin "19") (pinfunction "I/O[12]_19") (pintype "bidirectional"))
    )
    (net (code "24") (name "H3-BIN2") (class "Default")
      (node (ref "HB3") (pin "16") (pinfunction "BIN2_16") (pintype "input"))
      (node (ref "U6") (pin "20") (pinfunction "I/O[13]_20") (pintype "bidirectional"))
    )
    (net (code "25") (name "H3-BPWM") (class "Default")
      (node (ref "HB3") (pin "15") (pinfunction "PWMB_15") (pintype "input"))
      (node (ref "U6") (pin "21") (pinfunction "I/O[14]_21") (pintype "bidirectional"))
    )
    (net (code "26") (name "H4-AIN1") (class "Default")
      (node (ref "HB4") (pin "21") (pinfunction "AIN1_21") (pintype "input"))
      (node (ref "U6") (pin "2") (pinfunction "I/O[3]_2") (pintype "bidirectional"))
    )
    (net (code "27") (name "H4-AIN2") (class "Default")
      (node (ref "HB4") (pin "22") (pinfunction "AIN2_22") (pintype "input"))
      (node (ref "U6") (pin "1") (pinfunction "I/O[2]_1") (pintype "bidirectional"))
    )
    (net (code "28") (name "H4-APWM") (class "Default")
      (node (ref "HB4") (pin "23") (pinfunction "PWMA_23") (pintype "input"))
      (node (ref "U6") (pin "28") (pinfunction "I/O[1]_28") (pintype "bidirectional"))
    )
    (net (code "29") (name "H4-BIN1") (class "Default")
      (node (ref "HB4") (pin "17") (pinfunction "BIN1_17") (pintype "input"))
      (node (ref "U6") (pin "5") (pinfunction "I/O[4]_5") (pintype "bidirectional"))
    )
    (net (code "30") (name "H4-BIN2") (class "Default")
      (node (ref "HB4") (pin "16") (pinfunction "BIN2_16") (pintype "input"))
      (node (ref "U6") (pin "6") (pinfunction "I/O[5]_6") (pintype "bidirectional"))
    )
    (net (code "31") (name "H4-BPWM") (class "Default")
      (node (ref "HB4") (pin "15") (pinfunction "PWMB_15") (pintype "input"))
      (node (ref "U6") (pin "7") (pinfunction "I/O[6]_7") (pintype "bidirectional"))
    )
    (net (code "32") (name "IMU-BOOT") (class "Default")
      (node (ref "R16") (pin "1") (pinfunction "1_1") (pintype "passive"))
      (node (ref "TP17") (pin "P$1") (pinfunction "1_P$1") (pintype "bidirectional"))
      (node (ref "U4") (pin "4") (pinfunction "~{BOOT}_4") (pintype "bidirectional"))
      (node (ref "U9") (pin "16") (pinfunction "13-IO_16") (pintype "bidirectional"))
    )
    (net (code "33") (name "IMU-INT") (class "Default")
      (node (ref "TP4") (pin "P$1") (pinfunction "1_P$1") (pintype "bidirectional"))
      (node (ref "U4") (pin "14") (pinfunction "~{H_INT}_14") (pintype "bidirectional"))
      (node (ref "U9") (pin "11") (pinfunction "26-IOD_11") (pintype "bidirectional"))
    )
    (net (code "34") (name "IMU-RST") (class "Default")
      (node (ref "TP5") (pin "P$1") (pinfunction "1_P$1") (pintype "bidirectional"))
      (node (ref "U4") (pin "11") (pinfunction "~{RST}_11") (pintype "bidirectional"))
      (node (ref "U9") (pin "12") (pinfunction "27-IO_12") (pintype "bidirectional"))
    )
    (net (code "35") (name "IO1-RST") (class "Default")
      (node (ref "TP3") (pin "P$1") (pinfunction "1_P$1") (pintype "bidirectional"))
      (node (ref "U5") (pin "23") (pinfunction "~{RESET}_23") (pintype "bidirectional"))
      (node (ref "U9") (pin "10") (pinfunction "25-IOD_10") (pintype "bidirectional"))
    )
    (net (code "36") (name "IO2-RST") (class "Default")
      (node (ref "TP16") (pin "P$1") (pinfunction "1_P$1") (pintype "bidirectional"))
      (node (ref "U6") (pin "23") (pinfunction "~{RESET}_23") (pintype "bidirectional"))
      (node (ref "U9") (pin "26") (pinfunction "4-IO_26") (pintype "bidirectional"))
    )
    (net (code "37") (name "Net-(D2-PadC)") (class "Default")
      (node (ref "D2") (pin "C") (pinfunction "C_C") (pintype "passive"))
      (node (ref "R2") (pin "1") (pinfunction "1_1") (pintype "passive"))
    )
    (net (code "38") (name "Net-(HB1-AO1')") (class "Default")
      (node (ref "HB1") (pin "1") (pinfunction "AO1_1") (pintype "output"))
      (node (ref "HB1") (pin "2") (pinfunction "AO1'_2") (pintype "output"))
      (node (ref "J8") (pin "2") (pinfunction "1_2") (pintype "passive"))
    )
    (net (code "39") (name "Net-(HB1-AO2')") (class "Default")
      (node (ref "HB1") (pin "5") (pinfunction "AO2_5") (pintype "output"))
      (node (ref "HB1") (pin "6") (pinfunction "AO2'_6") (pintype "output"))
      (node (ref "J8") (pin "1") (pinfunction "2_1") (pintype "passive"))
    )
    (net (code "40") (name "Net-(HB1-BO1')") (class "Default")
      (node (ref "HB1") (pin "11") (pinfunction "BO1_11") (pintype "output"))
      (node (ref "HB1") (pin "12") (pinfunction "BO1'_12") (pintype "output"))
      (node (ref "J9") (pin "1") (pinfunction "2_1") (pintype "passive"))
    )
    (net (code "41") (name "Net-(HB1-BO2')") (class "Default")
      (node (ref "HB1") (pin "7") (pinfunction "BO2_7") (pintype "output"))
      (node (ref "HB1") (pin "8") (pinfunction "BO2'_8") (pintype "output"))
      (node (ref "J9") (pin "2") (pinfunction "1_2") (pintype "passive"))
    )
    (net (code "42") (name "Net-(HB2-AO1')") (class "Default")
      (node (ref "HB2") (pin "1") (pinfunction "AO1_1") (pintype "output"))
      (node (ref "HB2") (pin "2") (pinfunction "AO1'_2") (pintype "output"))
      (node (ref "J10") (pin "2") (pinfunction "1_2") (pintype "passive"))
    )
    (net (code "43") (name "Net-(HB2-AO2')") (class "Default")
      (node (ref "HB2") (pin "5") (pinfunction "AO2_5") (pintype "output"))
      (node (ref "HB2") (pin "6") (pinfunction "AO2'_6") (pintype "output"))
      (node (ref "J10") (pin "1") (pinfunction "2_1") (pintype "passive"))
    )
    (net (code "44") (name "Net-(HB2-BO1')") (class "Default")
      (node (ref "HB2") (pin "11") (pinfunction "BO1_11") (pintype "output"))
      (node (ref "HB2") (pin "12") (pinfunction "BO1'_12") (pintype "output"))
      (node (ref "J11") (pin "1") (pinfunction "2_1") (pintype "passive"))
    )
    (net (code "45") (name "Net-(HB2-BO2')") (class "Default")
      (node (ref "HB2") (pin "7") (pinfunction "BO2_7") (pintype "output"))
      (node (ref "HB2") (pin "8") (pinfunction "BO2'_8") (pintype "output"))
      (node (ref "J11") (pin "2") (pinfunction "1_2") (pintype "passive"))
    )
    (net (code "46") (name "Net-(HB3-AO1')") (class "Default")
      (node (ref "HB3") (pin "1") (pinfunction "AO1_1") (pintype "output"))
      (node (ref "HB3") (pin "2") (pinfunction "AO1'_2") (pintype "output"))
      (node (ref "J12") (pin "2") (pinfunction "1_2") (pintype "passive"))
    )
    (net (code "47") (name "Net-(HB3-AO2')") (class "Default")
      (node (ref "HB3") (pin "5") (pinfunction "AO2_5") (pintype "output"))
      (node (ref "HB3") (pin "6") (pinfunction "AO2'_6") (pintype "output"))
      (node (ref "J12") (pin "1") (pinfunction "2_1") (pintype "passive"))
    )
    (net (code "48") (name "Net-(HB3-BO1')") (class "Default")
      (node (ref "HB3") (pin "11") (pinfunction "BO1_11") (pintype "output"))
      (node (ref "HB3") (pin "12") (pinfunction "BO1'_12") (pintype "output"))
      (node (ref "J13") (pin "1") (pinfunction "2_1") (pintype "passive"))
    )
    (net (code "49") (name "Net-(HB3-BO2')") (class "Default")
      (node (ref "HB3") (pin "7") (pinfunction "BO2_7") (pintype "output"))
      (node (ref "HB3") (pin "8") (pinfunction "BO2'_8") (pintype "output"))
      (node (ref "J13") (pin "2") (pinfunction "1_2") (pintype "passive"))
    )
    (net (code "50") (name "Net-(HB4-AO1')") (class "Default")
      (node (ref "HB4") (pin "1") (pinfunction "AO1_1") (pintype "output"))
      (node (ref "HB4") (pin "2") (pinfunction "AO1'_2") (pintype "output"))
      (node (ref "J14") (pin "2") (pinfunction "1_2") (pintype "passive"))
    )
    (net (code "51") (name "Net-(HB4-AO2')") (class "Default")
      (node (ref "HB4") (pin "5") (pinfunction "AO2_5") (pintype "output"))
      (node (ref "HB4") (pin "6") (pinfunction "AO2'_6") (pintype "output"))
      (node (ref "J14") (pin "1") (pinfunction "2_1") (pintype "passive"))
    )
    (net (code "52") (name "Net-(HB4-BO1')") (class "Default")
      (node (ref "HB4") (pin "11") (pinfunction "BO1_11") (pintype "output"))
      (node (ref "HB4") (pin "12") (pinfunction "BO1'_12") (pintype "output"))
      (node (ref "J15") (pin "1") (pinfunction "2_1") (pintype "passive"))
    )
    (net (code "53") (name "Net-(HB4-BO2')") (class "Default")
      (node (ref "HB4") (pin "7") (pinfunction "BO2_7") (pintype "output"))
      (node (ref "HB4") (pin "8") (pinfunction "BO2'_8") (pintype "output"))
      (node (ref "J15") (pin "2") (pinfunction "1_2") (pintype "passive"))
    )
    (net (code "54") (name "Net-(Q1-B)") (class "Default")
      (node (ref "Q1") (pin "1") (pinfunction "B_1") (pintype "passive"))
      (node (ref "R10") (pin "2") (pinfunction "2_2") (pintype "passive"))
    )
    (net (code "55") (name "Net-(Q2-B)") (class "Default")
      (node (ref "Q2") (pin "1") (pinfunction "B_1") (pintype "passive"))
      (node (ref "R9") (pin "2") (pinfunction "2_2") (pintype "passive"))
    )
    (net (code "56") (name "Net-(Q3-S)") (class "Default")
      (node (ref "C6") (pin "1") (pinfunction "1_1") (pintype "passive"))
      (node (ref "D1") (pin "C") (pinfunction "C_C") (pintype "passive"))
      (node (ref "Q3") (pin "2") (pinfunction "S_2") (pintype "passive"))
      (node (ref "S1") (pin "3") (pinfunction "S_3") (pintype "passive"))
      (node (ref "U2") (pin "1") (pinfunction "IN_1") (pintype "power_in"))
    )
    (net (code "57") (name "Net-(S1-P)") (class "Default")
      (node (ref "S1") (pin "2") (pinfunction "P_2") (pintype "passive"))
      (node (ref "U2") (pin "3") (pinfunction "EN_3") (pintype "input"))
    )
    (net (code "58") (name "Net-(TP6-1)") (class "Default")
      (node (ref "TP6") (pin "P$1") (pinfunction "1_P$1") (pintype "bidirectional"))
      (node (ref "U9") (pin "13") (pinfunction "14-IO_13") (pintype "bidirectional"))
    )
    (net (code "59") (name "Net-(TP7-1)") (class "Default")
      (node (ref "TP7") (pin "P$1") (pinfunction "1_P$1") (pintype "bidirectional"))
      (node (ref "U9") (pin "7") (pinfunction "35-IA_7") (pintype "bidirectional"))
    )
    (net (code "60") (name "Net-(TP8-1)") (class "Default")
      (node (ref "TP8") (pin "P$1") (pinfunction "1_P$1") (pintype "bidirectional"))
      (node (ref "U9") (pin "6") (pinfunction "34-IA_6") (pintype "bidirectional"))
    )
    (net (code "61") (name "Net-(TP9-1)") (class "Default")
      (node (ref "TP9") (pin "P$1") (pinfunction "1_P$1") (pintype "bidirectional"))
      (node (ref "U9") (pin "5") (pinfunction "39-I_5") (pintype "bidirectional"))
    )
    (net (code "62") (name "Net-(TP10-1)") (class "Default")
      (node (ref "TP10") (pin "P$1") (pinfunction "1_P$1") (pintype "bidirectional"))
      (node (ref "U9") (pin "4") (pinfunction "36-I_4") (pintype "bidirectional"))
    )
    (net (code "63") (name "Net-(U1-2)") (class "Default")
      (node (ref "R7") (pin "1") (pinfunction "1_1") (pintype "passive"))
      (node (ref "U1") (pin "BLUE") (pinfunction "2_BLUE") (pintype "passive"))
    )
    (net (code "64") (name "Net-(U1-3)") (class "Default")
      (node (ref "R6") (pin "1") (pinfunction "1_1") (pintype "passive"))
      (node (ref "U1") (pin "GREEN") (pinfunction "3_GREEN") (pintype "passive"))
    )
    (net (code "65") (name "Net-(U1-4)") (class "Default")
      (node (ref "R5") (pin "1") (pinfunction "1_1") (pintype "passive"))
      (node (ref "U1") (pin "RED") (pinfunction "4_RED") (pintype "passive"))
    )
    (net (code "66") (name "Net-(U3-PROG)") (class "Default")
      (node (ref "JP1") (pin "1") (pinfunction "1_1") (pintype "passive"))
      (node (ref "R4") (pin "2") (pinfunction "2_2") (pintype "passive"))
      (node (ref "U3") (pin "5") (pinfunction "PROG_5") (pintype "input"))
    )
    (net (code "67") (name "Net-(U3-STAT)") (class "Default")
      (node (ref "R2") (pin "2") (pinfunction "2_2") (pintype "passive"))
      (node (ref "U3") (pin "1") (pinfunction "STAT_1") (pintype "output"))
    )
    (net (code "68") (name "Net-(U4-CAP)") (class "Default")
      (node (ref "C1") (pin "1") (pinfunction "1_1") (pintype "passive"))
      (node (ref "U4") (pin "9") (pinfunction "CAP_9") (pintype "bidirectional"))
    )
    (net (code "69") (name "Net-(U4-S_SCL)") (class "Default")
      (node (ref "R15") (pin "1") (pinfunction "1_1") (pintype "passive"))
      (node (ref "U4") (pin "15") (pinfunction "S_SCL_15") (pintype "bidirectional"))
    )
    (net (code "70") (name "Net-(U4-S_SDA)") (class "Default")
      (node (ref "R8") (pin "1") (pinfunction "1_1") (pintype "passive"))
      (node (ref "U4") (pin "16") (pinfunction "S_SDA_16") (pintype "bidirectional"))
    )
    (net (code "71") (name "Net-(U7A-D+)") (class "Default")
      (node (ref "J1") (pin "D+") (pinfunction "D+_D+") (pintype "bidirectional"))
      (node (ref "U7") (pin "3") (pinfunction "D+_3") (pintype "bidirectional"))
    )
    (net (code "72") (name "Net-(U7A-D-)") (class "Default")
      (node (ref "J1") (pin "D-") (pinfunction "D-_D-") (pintype "bidirectional"))
      (node (ref "U7") (pin "4") (pinfunction "D-_4") (pintype "bidirectional"))
    )
    (net (code "73") (name "RED") (class "Default")
      (node (ref "R5") (pin "2") (pinfunction "2_2") (pintype "passive"))
      (node (ref "TP20") (pin "P$1") (pinfunction "1_P$1") (pintype "bidirectional"))
      (node (ref "U9") (pin "31") (pinfunction "19-IO_31") (pintype "bidirectional"))
    )
    (net (code "74") (name "RTS") (class "Default")
      (node (ref "Q1") (pin "2") (pinfunction "E_2") (pintype "passive"))
      (node (ref "R9") (pin "1") (pinfunction "1_1") (pintype "passive"))
      (node (ref "U7") (pin "19") (pinfunction "RTS_19") (pintype "output"))
    )
    (net (code "75") (name "RX") (class "Default")
      (node (ref "U7") (pin "21") (pinfunction "TXD_21") (pintype "output"))
      (node (ref "U9") (pin "34") (pinfunction "RX_34") (pintype "bidirectional"))
    )
    (net (code "76") (name "S1-SIG") (class "Default")
      (node (ref "J4") (pin "3") (pinfunction "3_3") (pintype "passive"))
      (node (ref "TP2") (pin "P$1") (pinfunction "1_P$1") (pintype "bidirectional"))
      (node (ref "U9") (pin "9") (pinfunction "33-IOA_9") (pintype "bidirectional"))
    )
    (net (code "77") (name "S2-SIG") (class "Default")
      (node (ref "J5") (pin "3") (pinfunction "3_3") (pintype "passive"))
      (node (ref "TP1") (pin "P$1") (pinfunction "1_P$1") (pintype "bidirectional"))
      (node (ref "U9") (pin "8") (pinfunction "32-IOA_8") (pintype "bidirectional"))
    )
    (net (code "78") (name "S3-SIG") (class "Default")
      (node (ref "J6") (pin "3") (pinfunction "3_3") (pintype "passive"))
      (node (ref "TP14") (pin "P$1") (pinfunction "1_P$1") (pintype "bidirectional"))
      (node (ref "U9") (pin "37") (pinfunction "23-IO_37") (pintype "bidirectional"))
    )
    (net (code "79") (name "S4-SIG") (class "Default")
      (node (ref "J7") (pin "3") (pinfunction "3_3") (pintype "passive"))
      (node (ref "TP15") (pin "P$1") (pinfunction "1_P$1") (pintype "bidirectional"))
      (node (ref "U9") (pin "27") (pinfunction "16-IO_27") (pintype "bidirectional"))
    )
    (net (code "80") (name "SCL") (class "Default")
      (node (ref "R14") (pin "2") (pinfunction "2_2") (pintype "passive"))
      (node (ref "TP18") (pin "P$1") (pinfunction "1_P$1") (pintype "bidirectional"))
      (node (ref "U10") (pin "P$7") (pinfunction "SCL_P$7") (pintype "output"))
      (node (ref "U4") (pin "19") (pinfunction "H_SCL/SCLK/RX_19") (pintype "bidirectional"))
      (node (ref "U5") (pin "25") (pinfunction "SCL_25") (pintype "bidirectional"))
      (node (ref "U6") (pin "25") (pinfunction "SCL_25") (pintype "bidirectional"))
      (node (ref "U9") (pin "36") (pinfunction "22-IO_36") (pintype "bidirectional"))
    )
    (net (code "81") (name "SDA") (class "Default")
      (node (ref "R13") (pin "1") (pinfunction "1_1") (pintype "passive"))
      (node (ref "TP19") (pin "P$1") (pinfunction "1_P$1") (pintype "bidirectional"))
      (node (ref "U10") (pin "P$8") (pinfunction "SDA_P$8") (pintype "input"))
      (node (ref "U4") (pin "20") (pinfunction "H_SDA/MISO/TX_20") (pintype "bidirectional"))
      (node (ref "U5") (pin "24") (pinfunction "SDA_24") (pintype "bidirectional"))
      (node (ref "U6") (pin "24") (pinfunction "SDA_24") (pintype "bidirectional"))
      (node (ref "U9") (pin "33") (pinfunction "21-IO_33") (pintype "bidirectional"))
    )
    (net (code "82") (name "TX") (class "Default")
      (node (ref "U7") (pin "20") (pinfunction "RXD_20") (pintype "input"))
      (node (ref "U9") (pin "35") (pinfunction "TX_35") (pintype "bidirectional"))
    )
    (net (code "83") (name "VBAT") (class "Default")
      (node (ref "C11") (pin "1") (pinfunction "1_1") (pintype "passive"))
      (node (ref "C19") (pin "1") (pinfunction "1_1") (pintype "passive"))
      (node (ref "C22") (pin "1") (pinfunction "1_1") (pintype "passive"))
      (node (ref "C25") (pin "1") (pinfunction "1_1") (pintype "passive"))
      (node (ref "C28") (pin "+") (pinfunction "+_+") (pintype "passive"))
      (node (ref "C29") (pin "+") (pinfunction "+_+") (pintype "passive"))
      (node (ref "C3") (pin "1") (pinfunction "1_1") (pintype "passive"))
      (node (ref "C30") (pin "+") (pinfunction "+_+") (pintype "passive"))
      (node (ref "C31") (pin "+") (pinfunction "+_+") (pintype "passive"))
      (node (ref "C5") (pin "1") (pinfunction "1_1") (pintype "passive"))
      (node (ref "HB1") (pin "13") (pinfunction "VM2_13") (pintype "power_in"))
      (node (ref "HB1") (pin "14") (pinfunction "VM3_14") (pintype "power_in"))
      (node (ref "HB1") (pin "24") (pinfunction "VM1_24") (pintype "power_in"))
      (node (ref "HB2") (pin "13") (pinfunction "VM2_13") (pintype "power_in"))
      (node (ref "HB2") (pin "14") (pinfunction "VM3_14") (pintype "power_in"))
      (node (ref "HB2") (pin "24") (pinfunction "VM1_24") (pintype "power_in"))
      (node (ref "HB3") (pin "13") (pinfunction "VM2_13") (pintype "power_in"))
      (node (ref "HB3") (pin "14") (pinfunction "VM3_14") (pintype "power_in"))
      (node (ref "HB3") (pin "24") (pinfunction "VM1_24") (pintype "power_in"))
      (node (ref "HB4") (pin "13") (pinfunction "VM2_13") (pintype "power_in"))
      (node (ref "HB4") (pin "14") (pinfunction "VM3_14") (pintype "power_in"))
      (node (ref "HB4") (pin "24") (pinfunction "VM1_24") (pintype "power_in"))
      (node (ref "J2") (pin "2") (pinfunction "1_2") (pintype "passive"))
      (node (ref "J4") (pin "1") (pinfunction "1_1") (pintype "passive"))
      (node (ref "J5") (pin "1") (pinfunction "1_1") (pintype "passive"))
      (node (ref "J6") (pin "1") (pinfunction "1_1") (pintype "passive"))
      (node (ref "J7") (pin "1") (pinfunction "1_1") (pintype "passive"))
      (node (ref "Q3") (pin "3") (pinfunction "D_3") (pintype "passive"))
      (node (ref "U10") (pin "P$2") (pinfunction "CELL_P$2") (pintype "input"))
      (node (ref "U10") (pin "P$3") (pinfunction "VDD_P$3") (pintype "bidirectional"))
      (node (ref "U3") (pin "3") (pinfunction "VBAT_3") (pintype "power_in"))
    )
    (net (code "84") (name "VUSB") (class "Default")
      (node (ref "C9") (pin "1") (pinfunction "1_1") (pintype "passive"))
      (node (ref "D1") (pin "A") (pinfunction "A_A") (pintype "passive"))
      (node (ref "D2") (pin "A") (pinfunction "A_A") (pintype "passive"))
      (node (ref "J1") (pin "VBUS") (pinfunction "VBUS_VBUS") (pintype "power_in"))
      (node (ref "JP1") (pin "2") (pinfunction "2_2") (pintype "passive"))
      (node (ref "Q3") (pin "1") (pinfunction "G_1") (pintype "passive"))
      (node (ref "R12") (pin "2") (pinfunction "2_2") (pintype "passive"))
      (node (ref "U3") (pin "4") (pinfunction "VDD_4") (pintype "power_in"))
      (node (ref "U7") (pin "8") (pinfunction "VBUS_8") (pintype "power_in"))
    )
    (net (code "85") (name "unconnected-(J1-PadID)") (class "Default")
      (node (ref "J1") (pin "ID") (pinfunction "ID_ID") (pintype "bidirectional"))
    )
    (net (code "86") (name "unconnected-(U2-P4-Pad4)") (class "Default")
      (node (ref "U2") (pin "4") (pinfunction "P4_4") (pintype "bidirectional"))
    )
    (net (code "87") (name "unconnected-(U4-XIN32-Pad27)") (class "Default")
      (node (ref "U4") (pin "27") (pinfunction "XIN32_27") (pintype "bidirectional"))
    )
    (net (code "88") (name "unconnected-(U4-~{H_CS}-Pad18)") (class "Default")
      (node (ref "U4") (pin "18") (pinfunction "~{H_CS}_18") (pintype "bidirectional"))
    )
    (net (code "89") (name "unconnected-(U5-I{slash}O[0]-Pad27)") (class "Default")
      (node (ref "U5") (pin "27") (pinfunction "I/O[0]_27") (pintype "bidirectional"))
    )
    (net (code "90") (name "unconnected-(U5-I{slash}O[7]-Pad8)") (class "Default")
      (node (ref "U5") (pin "8") (pinfunction "I/O[7]_8") (pintype "bidirectional"))
    )
    (net (code "91") (name "unconnected-(U5-I{slash}O[8]-Pad13)") (class "Default")
      (node (ref "U5") (pin "13") (pinfunction "I/O[8]_13") (pintype "bidirectional"))
    )
    (net (code "92") (name "unconnected-(U5-I{slash}O[15]-Pad22)") (class "Default")
      (node (ref "U5") (pin "22") (pinfunction "I/O[15]_22") (pintype "bidirectional"))
    )
    (net (code "93") (name "unconnected-(U5-OSCIO-Pad11)") (class "Default")
      (node (ref "U5") (pin "11") (pinfunction "OSCIO_11") (pintype "bidirectional"))
    )
    (net (code "94") (name "unconnected-(U5-~{INT}-Pad9)") (class "Default")
      (node (ref "U5") (pin "9") (pinfunction "~{INT}_9") (pintype "bidirectional"))
    )
    (net (code "95") (name "unconnected-(U6-I{slash}O[0]-Pad27)") (class "Default")
      (node (ref "U6") (pin "27") (pinfunction "I/O[0]_27") (pintype "bidirectional"))
    )
    (net (code "96") (name "unconnected-(U6-I{slash}O[7]-Pad8)") (class "Default")
      (node (ref "U6") (pin "8") (pinfunction "I/O[7]_8") (pintype "bidirectional"))
    )
    (net (code "97") (name "unconnected-(U6-I{slash}O[8]-Pad13)") (class "Default")
      (node (ref "U6") (pin "13") (pinfunction "I/O[8]_13") (pintype "bidirectional"))
    )
    (net (code "98") (name "unconnected-(U6-I{slash}O[15]-Pad22)") (class "Default")
      (node (ref "U6") (pin "22") (pinfunction "I/O[15]_22") (pintype "bidirectional"))
    )
    (net (code "99") (name "unconnected-(U6-OSCIO-Pad11)") (class "Default")
      (node (ref "U6") (pin "11") (pinfunction "OSCIO_11") (pintype "bidirectional"))
    )
    (net (code "100") (name "unconnected-(U6-~{INT}-Pad9)") (class "Default")
      (node (ref "U6") (pin "9") (pinfunction "~{INT}_9") (pintype "bidirectional"))
    )
    (net (code "101") (name "unconnected-(U7A-#RST-Pad9)") (class "Default")
      (node (ref "U7") (pin "9") (pinfunction "#RST_9") (pintype "bidirectional"))
    )
    (net (code "102") (name "unconnected-(U7A-#SUSPEND-Pad15)") (class "Default")
      (node (ref "U7") (pin "15") (pinfunction "#SUSPEND_15") (pintype "output"))
    )
    (net (code "103") (name "unconnected-(U7A-CTS-Pad18)") (class "Default")
      (node (ref "U7") (pin "18") (pinfunction "CTS_18") (pintype "input"))
    )
    (net (code "104") (name "unconnected-(U7A-DCD-Pad24)") (class "Default")
      (node (ref "U7") (pin "24") (pinfunction "DCD_24") (pintype "input"))
    )
    (net (code "105") (name "unconnected-(U7A-DSR-Pad22)") (class "Default")
      (node (ref "U7") (pin "22") (pinfunction "DSR_22") (pintype "input"))
    )
    (net (code "106") (name "unconnected-(U7A-GPIO0{slash}TXLED-Pad14)") (class "Default")
      (node (ref "U7") (pin "14") (pinfunction "GPIO0/TXLED_14") (pintype "bidirectional"))
    )
    (net (code "107") (name "unconnected-(U7A-GPIO1{slash}RXLED-Pad13)") (class "Default")
      (node (ref "U7") (pin "13") (pinfunction "GPIO1/RXLED_13") (pintype "bidirectional"))
    )
    (net (code "108") (name "unconnected-(U7A-GPIO2-Pad12)") (class "Default")
      (node (ref "U7") (pin "12") (pinfunction "GPIO2_12") (pintype "bidirectional"))
    )
    (net (code "109") (name "unconnected-(U7A-GPIO3-Pad11)") (class "Default")
      (node (ref "U7") (pin "11") (pinfunction "GPIO3_11") (pintype "bidirectional"))
    )
    (net (code "110") (name "unconnected-(U7A-NC-Pad10)") (class "Default")
      (node (ref "U7") (pin "10") (pinfunction "NC_10") (pintype "no_connect"))
    )
    (net (code "111") (name "unconnected-(U7A-RI-Pad1)") (class "Default")
      (node (ref "U7") (pin "1") (pinfunction "RI_1") (pintype "input"))
    )
    (net (code "112") (name "unconnected-(U7A-SUSPEND-Pad17)") (class "Default")
      (node (ref "U7") (pin "17") (pinfunction "SUSPEND_17") (pintype "output"))
    )
    (net (code "113") (name "unconnected-(U7A-VPP-Pad16)") (class "Default")
      (node (ref "U7") (pin "16") (pinfunction "VPP_16") (pintype "bidirectional"))
    )
    (net (code "114") (name "unconnected-(U9-2-Pad24)") (class "Default")
      (node (ref "U9") (pin "24") (pinfunction "2_24") (pintype "bidirectional"))
    )
    (net (code "115") (name "unconnected-(U9-5-Pad29)") (class "Default")
      (node (ref "U9") (pin "29") (pinfunction "5_29") (pintype "bidirectional"))
    )
    (net (code "116") (name "unconnected-(U9-12-Pad14)") (class "Default")
      (node (ref "U9") (pin "14") (pinfunction "12_14") (pintype "bidirectional"))
    )
    (net (code "117") (name "unconnected-(U9-15-Pad23)") (class "Default")
      (node (ref "U9") (pin "23") (pinfunction "15_23") (pintype "bidirectional"))
    )
    (net (code "118") (name "unconnected-(U9-NC-Pad32)") (class "Default")
      (node (ref "U9") (pin "32") (pinfunction "NC_32") (pintype "bidirectional"))
    )
    (net (code "119") (name "unconnected-(U9-SCK-Pad20)") (class "Default")
      (node (ref "U9") (pin "20") (pinfunction "SCK_20") (pintype "bidirectional"))
    )
    (net (code "120") (name "unconnected-(U9-SCS-Pad19)") (class "Default")
      (node (ref "U9") (pin "19") (pinfunction "SCS_19") (pintype "bidirectional"))
    )
    (net (code "121") (name "unconnected-(U9-SDI-Pad22)") (class "Default")
      (node (ref "U9") (pin "22") (pinfunction "SDI_22") (pintype "bidirectional"))
    )
    (net (code "122") (name "unconnected-(U9-SDO-Pad21)") (class "Default")
      (node (ref "U9") (pin "21") (pinfunction "SDO_21") (pintype "bidirectional"))
    )
    (net (code "123") (name "unconnected-(U9-SHD-Pad17)") (class "Default")
      (node (ref "U9") (pin "17") (pinfunction "SHD_17") (pintype "bidirectional"))
    )
    (net (code "124") (name "unconnected-(U9-SWP-Pad18)") (class "Default")
      (node (ref "U9") (pin "18") (pinfunction "SWP_18") (pintype "bidirectional"))
    )
    (net (code "125") (name "unconnected-(U10-~{ALRT}-PadP$5)") (class "Default")
      (node (ref "U10") (pin "P$5") (pinfunction "~{ALRT}_P$5") (pintype "bidirectional"))
    )
  )
)
